# Shield.net
KiCad netlist of a schematic drawn in Altium Designer
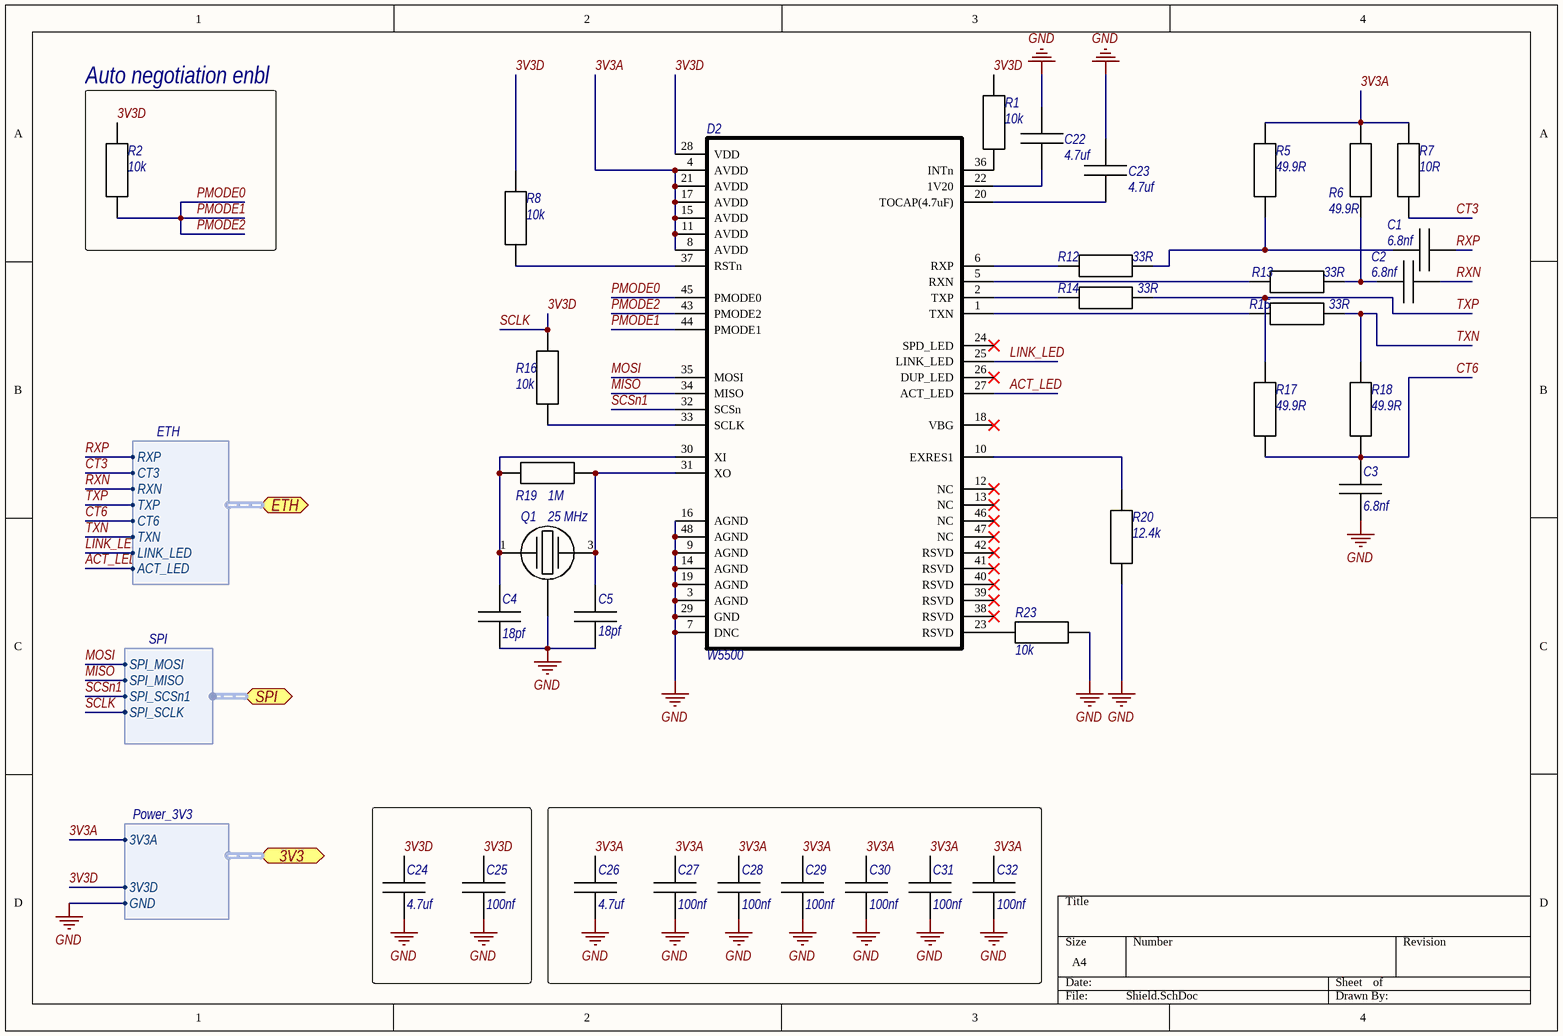
[diagram p0: Shield.SchDoc]

(export (version "E")
  (design (tool "Eeschema 10.0.6"))
  (components
    (comp (ref "C1") (value "6.8nf") (libsource (lib "Passive") (part "Capacitor")))
    (comp (ref "C2") (value "6.8nf") (libsource (lib "Passive") (part "Capacitor")))
    (comp (ref "C3") (value "6.8nf") (libsource (lib "Passive") (part "Capacitor")))
    (comp (ref "C4") (value "18pf") (libsource (lib "Passive") (part "Capacitor")))
    (comp (ref "C5") (value "18pf") (libsource (lib "Passive") (part "Capacitor")))
    (comp (ref "C22") (value "4.7uf") (libsource (lib "Passive") (part "Capacitor")))
    (comp (ref "C23") (value "4.7uf") (libsource (lib "Passive") (part "Capacitor")))
    (comp (ref "C24") (value "4.7uf") (libsource (lib "Passive") (part "Capacitor")))
    (comp (ref "C25") (value "100nf") (libsource (lib "Passive") (part "Capacitor")))
    (comp (ref "C26") (value "4.7uf") (libsource (lib "Passive") (part "Capacitor")))
    (comp (ref "C27") (value "100nf") (libsource (lib "Passive") (part "Capacitor")))
    (comp (ref "C28") (value "100nf") (libsource (lib "Passive") (part "Capacitor")))
    (comp (ref "C29") (value "100nf") (libsource (lib "Passive") (part "Capacitor")))
    (comp (ref "C30") (value "100nf") (libsource (lib "Passive") (part "Capacitor")))
    (comp (ref "C31") (value "100nf") (libsource (lib "Passive") (part "Capacitor")))
    (comp (ref "C32") (value "100nf") (libsource (lib "Passive") (part "Capacitor")))
    (comp (ref "D2")
      (value "W5500")
      (footprint "LQFP-48 7.0 x 7.0 x 1.6")
      (libsource (lib "ic") (part "W5500"))
    )
    (comp (ref "Q1") (value "25 MHz") (libsource (lib "Passive") (part "Oscillator")))
    (comp (ref "R1") (value "10k") (description "Resistor") (libsource (lib "") (part "Resistor_2")))
    (comp (ref "R2") (value "10k") (description "Resistor") (libsource (lib "") (part "Resistor_2")))
    (comp (ref "R5") (value "49.9R") (description "Resistor") (libsource (lib "") (part "Resistor_1")))
    (comp (ref "R6") (value "49.9R") (description "Resistor") (libsource (lib "") (part "Resistor_1")))
    (comp (ref "R7") (value "10R") (description "Resistor") (libsource (lib "") (part "Resistor_1")))
    (comp (ref "R8") (value "10k") (description "Resistor") (libsource (lib "") (part "Resistor_2")))
    (comp (ref "R12") (value "33R") (description "Resistor") (libsource (lib "Passive") (part "Resistor")))
    (comp (ref "R13") (value "33R") (description "Resistor") (libsource (lib "Passive") (part "Resistor")))
    (comp (ref "R14") (value "33R") (description "Resistor") (libsource (lib "Passive") (part "Resistor")))
    (comp (ref "R15") (value "33R") (description "Resistor") (libsource (lib "Passive") (part "Resistor")))
    (comp (ref "R16") (value "10k") (description "Resistor") (libsource (lib "") (part "Resistor_1")))
    (comp (ref "R17") (value "49.9R") (description "Resistor") (libsource (lib "") (part "Resistor_1")))
    (comp (ref "R18") (value "49.9R") (description "Resistor") (libsource (lib "") (part "Resistor_1")))
    (comp (ref "R19") (value "1M") (description "Resistor") (libsource (lib "Passive") (part "Resistor")))
    (comp (ref "R20") (value "12.4k") (description "Resistor") (libsource (lib "") (part "Resistor_2")))
    (comp (ref "R23") (value "10k") (description "Resistor") (libsource (lib "Passive") (part "Resistor")))
  )
  (nets
    (net (code "4") (name "/3V3A") (class "Default")
      (node (ref "C26") (pin "2") (pinfunction "2_2") (pintype "passive"))
      (node (ref "C27") (pin "2") (pinfunction "2_2") (pintype "passive"))
      (node (ref "C28") (pin "2") (pinfunction "2_2") (pintype "passive"))
      (node (ref "C29") (pin "2") (pinfunction "2_2") (pintype "passive"))
      (node (ref "C30") (pin "2") (pinfunction "2_2") (pintype "passive"))
      (node (ref "C31") (pin "2") (pinfunction "2_2") (pintype "passive"))
      (node (ref "C32") (pin "2") (pinfunction "2_2") (pintype "passive"))
      (node (ref "D2") (pin "11") (pinfunction "AVDD_11") (pintype "passive"))
      (node (ref "D2") (pin "15") (pinfunction "AVDD_15") (pintype "passive"))
      (node (ref "D2") (pin "17") (pinfunction "AVDD_17") (pintype "passive"))
      (node (ref "D2") (pin "21") (pinfunction "AVDD_21") (pintype "passive"))
      (node (ref "D2") (pin "4") (pinfunction "AVDD_4") (pintype "passive"))
      (node (ref "D2") (pin "8") (pinfunction "AVDD_8") (pintype "passive"))
      (node (ref "R5") (pin "1") (pinfunction "1_1") (pintype "passive"))
      (node (ref "R6") (pin "1") (pinfunction "1_1") (pintype "passive"))
      (node (ref "R7") (pin "1") (pinfunction "1_1") (pintype "passive"))
    )
    (net (code "5") (name "/3V3D") (class "Default")
      (node (ref "C24") (pin "2") (pinfunction "2_2") (pintype "passive"))
      (node (ref "C25") (pin "2") (pinfunction "2_2") (pintype "passive"))
      (node (ref "D2") (pin "28") (pinfunction "VDD_28") (pintype "passive"))
      (node (ref "R1") (pin "2") (pinfunction "2_2") (pintype "passive"))
      (node (ref "R16") (pin "1") (pinfunction "1_1") (pintype "passive"))
      (node (ref "R2") (pin "2") (pinfunction "2_2") (pintype "passive"))
      (node (ref "R8") (pin "2") (pinfunction "2_2") (pintype "passive"))
    )
    (net (code "6") (name "/ACT_LED") (class "Default")
      (node (ref "D2") (pin "27") (pinfunction "ACT_LED_27") (pintype "passive"))
    )
    (net (code "7") (name "/CT3") (class "Default")
      (node (ref "R7") (pin "2") (pinfunction "2_2") (pintype "passive"))
    )
    (net (code "8") (name "/CT6") (class "Default")
      (node (ref "C3") (pin "2") (pinfunction "2_2") (pintype "passive"))
      (node (ref "R17") (pin "2") (pinfunction "2_2") (pintype "passive"))
      (node (ref "R18") (pin "2") (pinfunction "2_2") (pintype "passive"))
    )
    (net (code "9") (name "/LINK_LED") (class "Default")
      (node (ref "D2") (pin "25") (pinfunction "LINK_LED_25") (pintype "passive"))
    )
    (net (code "10") (name "/MISO") (class "Default")
      (node (ref "D2") (pin "34") (pinfunction "MISO_34") (pintype "passive"))
    )
    (net (code "11") (name "/MOSI") (class "Default")
      (node (ref "D2") (pin "35") (pinfunction "MOSI_35") (pintype "passive"))
    )
    (net (code "12") (name "/PMODE0") (class "Default")
      (node (ref "D2") (pin "43") (pinfunction "PMODE2_43") (pintype "passive"))
      (node (ref "D2") (pin "44") (pinfunction "PMODE1_44") (pintype "passive"))
      (node (ref "D2") (pin "45") (pinfunction "PMODE0_45") (pintype "passive"))
      (node (ref "R2") (pin "1") (pinfunction "1_1") (pintype "passive"))
    )
    (net (code "13") (name "/RXN") (class "Default")
      (node (ref "C2") (pin "1") (pinfunction "1_1") (pintype "passive"))
    )
    (net (code "14") (name "/RXP") (class "Default")
      (node (ref "C1") (pin "1") (pinfunction "1_1") (pintype "passive"))
    )
    (net (code "15") (name "/SCSn1") (class "Default")
      (node (ref "D2") (pin "32") (pinfunction "SCSn_32") (pintype "passive"))
    )
    (net (code "16") (name "/TXN") (class "Default")
      (node (ref "R15") (pin "1") (pinfunction "1_1") (pintype "passive"))
      (node (ref "R18") (pin "1") (pinfunction "1_1") (pintype "passive"))
    )
    (net (code "17") (name "/TXP") (class "Default")
      (node (ref "R14") (pin "1") (pinfunction "1_1") (pintype "passive"))
      (node (ref "R17") (pin "1") (pinfunction "1_1") (pintype "passive"))
    )
    (net (code "21") (name "GND") (class "Default")
      (node (ref "C22") (pin "1") (pinfunction "1_1") (pintype "passive"))
      (node (ref "C23") (pin "1") (pinfunction "1_1") (pintype "passive"))
      (node (ref "C24") (pin "1") (pinfunction "1_1") (pintype "passive"))
      (node (ref "C25") (pin "1") (pinfunction "1_1") (pintype "passive"))
      (node (ref "C26") (pin "1") (pinfunction "1_1") (pintype "passive"))
      (node (ref "C27") (pin "1") (pinfunction "1_1") (pintype "passive"))
      (node (ref "C28") (pin "1") (pinfunction "1_1") (pintype "passive"))
      (node (ref "C29") (pin "1") (pinfunction "1_1") (pintype "passive"))
      (node (ref "C3") (pin "1") (pinfunction "1_1") (pintype "passive"))
      (node (ref "C30") (pin "1") (pinfunction "1_1") (pintype "passive"))
      (node (ref "C31") (pin "1") (pinfunction "1_1") (pintype "passive"))
      (node (ref "C32") (pin "1") (pinfunction "1_1") (pintype "passive"))
      (node (ref "C4") (pin "1") (pinfunction "1_1") (pintype "passive"))
      (node (ref "C5") (pin "1") (pinfunction "1_1") (pintype "passive"))
      (node (ref "D2") (pin "14") (pinfunction "AGND_14") (pintype "passive"))
      (node (ref "D2") (pin "16") (pinfunction "AGND_16") (pintype "passive"))
      (node (ref "D2") (pin "19") (pinfunction "AGND_19") (pintype "passive"))
      (node (ref "D2") (pin "29") (pinfunction "GND_29") (pintype "passive"))
      (node (ref "D2") (pin "3") (pinfunction "AGND_3") (pintype "passive"))
      (node (ref "D2") (pin "48") (pinfunction "AGND_48") (pintype "passive"))
      (node (ref "D2") (pin "7") (pinfunction "DNC_7") (pintype "passive"))
      (node (ref "D2") (pin "9") (pinfunction "AGND_9") (pintype "passive"))
      (node (ref "Q1") (pin "2") (pinfunction "2_2") (pintype "passive"))
      (node (ref "Q1") (pin "4") (pinfunction "4_4") (pintype "passive"))
      (node (ref "R20") (pin "1") (pinfunction "1_1") (pintype "passive"))
      (node (ref "R23") (pin "1") (pinfunction "1_1") (pintype "passive"))
    )
    (net (code "22") (name "Net-(C1-Pad2)") (class "Default")
      (node (ref "C1") (pin "2") (pinfunction "2_2") (pintype "passive"))
      (node (ref "R12") (pin "1") (pinfunction "1_1") (pintype "passive"))
      (node (ref "R5") (pin "2") (pinfunction "2_2") (pintype "passive"))
    )
    (net (code "23") (name "Net-(C2-Pad2)") (class "Default")
      (node (ref "C2") (pin "2") (pinfunction "2_2") (pintype "passive"))
      (node (ref "R13") (pin "1") (pinfunction "1_1") (pintype "passive"))
      (node (ref "R6") (pin "2") (pinfunction "2_2") (pintype "passive"))
    )
    (net (code "24") (name "Net-(D2-1V20)") (class "Default")
      (node (ref "C22") (pin "2") (pinfunction "2_2") (pintype "passive"))
      (node (ref "D2") (pin "22") (pinfunction "1V20_22") (pintype "passive"))
    )
    (net (code "25") (name "Net-(D2-EXRES1)") (class "Default")
      (node (ref "D2") (pin "10") (pinfunction "EXRES1_10") (pintype "passive"))
      (node (ref "R20") (pin "2") (pinfunction "2_2") (pintype "passive"))
    )
    (net (code "26") (name "Net-(D2-INTn)") (class "Default")
      (node (ref "D2") (pin "36") (pinfunction "INTn_36") (pintype "passive"))
      (node (ref "R1") (pin "1") (pinfunction "1_1") (pintype "passive"))
    )
    (net (code "27") (name "Net-(D2-RSTn)") (class "Default")
      (node (ref "D2") (pin "37") (pinfunction "RSTn_37") (pintype "passive"))
      (node (ref "R8") (pin "1") (pinfunction "1_1") (pintype "passive"))
    )
    (net (code "28") (name "Net-(D2-RSVD-Pad23)") (class "Default")
      (node (ref "D2") (pin "23") (pinfunction "RSVD_23") (pintype "passive"))
      (node (ref "R23") (pin "2") (pinfunction "2_2") (pintype "passive"))
    )
    (net (code "29") (name "Net-(D2-RXN)") (class "Default")
      (node (ref "D2") (pin "5") (pinfunction "RXN_5") (pintype "passive"))
      (node (ref "R13") (pin "2") (pinfunction "2_2") (pintype "passive"))
    )
    (net (code "30") (name "Net-(D2-RXP)") (class "Default")
      (node (ref "D2") (pin "6") (pinfunction "RXP_6") (pintype "passive"))
      (node (ref "R12") (pin "2") (pinfunction "2_2") (pintype "passive"))
    )
    (net (code "31") (name "Net-(D2-SCLK)") (class "Default")
      (node (ref "D2") (pin "33") (pinfunction "SCLK_33") (pintype "passive"))
      (node (ref "R16") (pin "2") (pinfunction "2_2") (pintype "passive"))
    )
    (net (code "32") (name "Net-(D2-TOCAP(4.7uF))") (class "Default")
      (node (ref "C23") (pin "2") (pinfunction "2_2") (pintype "passive"))
      (node (ref "D2") (pin "20") (pinfunction "TOCAP(4.7uF)_20") (pintype "passive"))
    )
    (net (code "33") (name "Net-(D2-TXN)") (class "Default")
      (node (ref "D2") (pin "1") (pinfunction "TXN_1") (pintype "passive"))
      (node (ref "R15") (pin "2") (pinfunction "2_2") (pintype "passive"))
    )
    (net (code "34") (name "Net-(D2-TXP)") (class "Default")
      (node (ref "D2") (pin "2") (pinfunction "TXP_2") (pintype "passive"))
      (node (ref "R14") (pin "2") (pinfunction "2_2") (pintype "passive"))
    )
    (net (code "35") (name "Net-(D2-XI)") (class "Default")
      (node (ref "C4") (pin "2") (pinfunction "2_2") (pintype "passive"))
      (node (ref "D2") (pin "30") (pinfunction "XI_30") (pintype "passive"))
      (node (ref "Q1") (pin "1") (pinfunction "1_1") (pintype "passive"))
      (node (ref "R19") (pin "2") (pinfunction "2_2") (pintype "passive"))
    )
    (net (code "36") (name "Net-(D2-XO)") (class "Default")
      (node (ref "C5") (pin "2") (pinfunction "2_2") (pintype "passive"))
      (node (ref "D2") (pin "31") (pinfunction "XO_31") (pintype "passive"))
      (node (ref "Q1") (pin "3") (pinfunction "3_3") (pintype "passive"))
      (node (ref "R19") (pin "1") (pinfunction "1_1") (pintype "passive"))
    )
    (net (code "37") (name "unconnected-(D2-DUP_LED-Pad26)") (class "Default")
      (node (ref "D2") (pin "26") (pinfunction "DUP_LED_26") (pintype "passive+no_connect"))
    )
    (net (code "38") (name "unconnected-(D2-NC-Pad12)") (class "Default")
      (node (ref "D2") (pin "12") (pinfunction "NC_12") (pintype "passive+no_connect"))
    )
    (net (code "39") (name "unconnected-(D2-NC-Pad13)") (class "Default")
      (node (ref "D2") (pin "13") (pinfunction "NC_13") (pintype "passive+no_connect"))
    )
    (net (code "40") (name "unconnected-(D2-NC-Pad46)") (class "Default")
      (node (ref "D2") (pin "46") (pinfunction "NC_46") (pintype "passive+no_connect"))
    )
    (net (code "41") (name "unconnected-(D2-NC-Pad47)") (class "Default")
      (node (ref "D2") (pin "47") (pinfunction "NC_47") (pintype "passive+no_connect"))
    )
    (net (code "42") (name "unconnected-(D2-RSVD-Pad38)") (class "Default")
      (node (ref "D2") (pin "38") (pinfunction "RSVD_38") (pintype "passive+no_connect"))
    )
    (net (code "43") (name "unconnected-(D2-RSVD-Pad39)") (class "Default")
      (node (ref "D2") (pin "39") (pinfunction "RSVD_39") (pintype "passive+no_connect"))
    )
    (net (code "44") (name "unconnected-(D2-RSVD-Pad40)") (class "Default")
      (node (ref "D2") (pin "40") (pinfunction "RSVD_40") (pintype "passive+no_connect"))
    )
    (net (code "45") (name "unconnected-(D2-RSVD-Pad41)") (class "Default")
      (node (ref "D2") (pin "41") (pinfunction "RSVD_41") (pintype "passive+no_connect"))
    )
    (net (code "46") (name "unconnected-(D2-RSVD-Pad42)") (class "Default")
      (node (ref "D2") (pin "42") (pinfunction "RSVD_42") (pintype "passive+no_connect"))
    )
    (net (code "47") (name "unconnected-(D2-SPD_LED-Pad24)") (class "Default")
      (node (ref "D2") (pin "24") (pinfunction "SPD_LED_24") (pintype "passive+no_connect"))
    )
    (net (code "48") (name "unconnected-(D2-VBG-Pad18)") (class "Default")
      (node (ref "D2") (pin "18") (pinfunction "VBG_18") (pintype "passive+no_connect"))
    )
  )
)
